# leds.net
KiCad netlist of a schematic drawn in Altium Designer
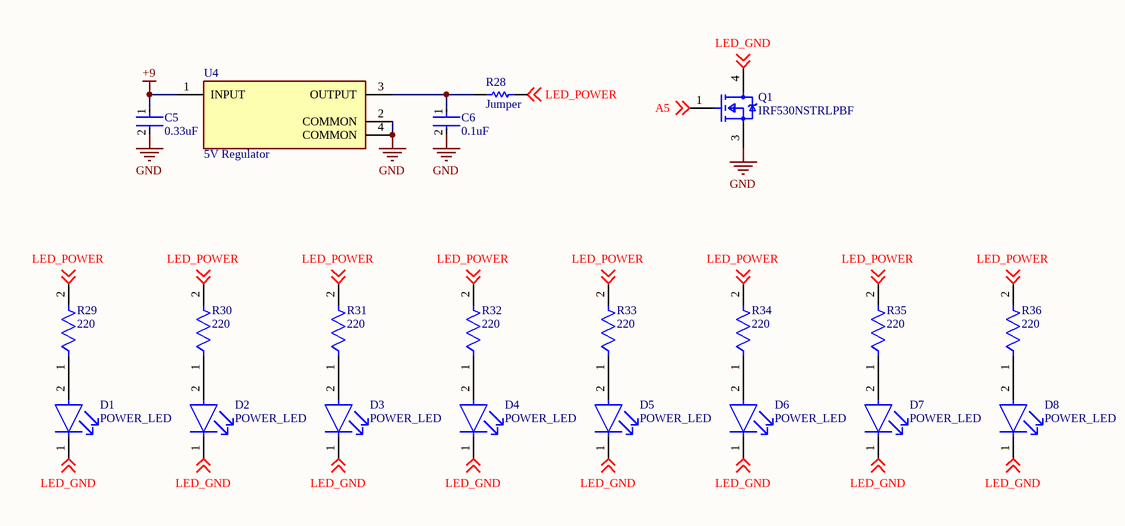
[diagram p0: leds.SchDoc]

(export (version "E")
  (design (tool "Eeschema 10.0.6"))
  (components
    (comp (ref "C5")
      (value "0.33uF")
      (footprint "FP-C0805C-DN-MFG")
      (description "C0805 0.33 μF X7R 30ppm/°C 10.00% 50 V")
      (fields (field (name "MANUFACTURER PART NUMBER") "C0805C334K5RACTU"))
      (libsource (lib "Altium Content Vault") (part "b4654b650e69147ec39a6b967a45e02"))
    )
    (comp (ref "C6")
      (value "0.1uF")
      (footprint "FP-C0805C-DN-MFG")
      (description "CAP CER 0.1UF 50V X7R 0805")
      (fields
        (field (name "MANUFACTURER PART NUMBER") "C0805C104K5RACTU")
        (field (name "MANUFACTURER") "KEMET")
      )
      (libsource (lib "Altium Content Vault") (part "b4654b650e69147ec39a6b967a45e02"))
    )
    (comp (ref "D1")
      (value "POWER_LED")
      (footprint "FP-APTD3216CGCK-MFG")
      (description "LED GREEN CLEAR 2SMD")
      (fields (field (name "MPN") "APTD3216CGCK"))
      (libsource (lib "Altium Content Vault") (part "8706943c75ba83719d021d2fdc84c58"))
    )
    (comp (ref "D2")
      (value "POWER_LED")
      (footprint "FP-APTD3216CGCK-MFG")
      (description "LED GREEN CLEAR 2SMD")
      (fields (field (name "MPN") "APTD3216CGCK"))
      (libsource (lib "Altium Content Vault") (part "8706943c75ba83719d021d2fdc84c58"))
    )
    (comp (ref "D3")
      (value "POWER_LED")
      (footprint "FP-APTD3216CGCK-MFG")
      (description "LED GREEN CLEAR 2SMD")
      (fields (field (name "MPN") "APTD3216CGCK"))
      (libsource (lib "Altium Content Vault") (part "8706943c75ba83719d021d2fdc84c58"))
    )
    (comp (ref "D4")
      (value "POWER_LED")
      (footprint "FP-APTD3216CGCK-MFG")
      (description "LED GREEN CLEAR 2SMD")
      (fields (field (name "MPN") "APTD3216CGCK"))
      (libsource (lib "Altium Content Vault") (part "8706943c75ba83719d021d2fdc84c58"))
    )
    (comp (ref "D5")
      (value "POWER_LED")
      (footprint "FP-APTD3216CGCK-MFG")
      (description "LED GREEN CLEAR 2SMD")
      (fields (field (name "MPN") "APTD3216CGCK"))
      (libsource (lib "Altium Content Vault") (part "8706943c75ba83719d021d2fdc84c58"))
    )
    (comp (ref "D6")
      (value "POWER_LED")
      (footprint "FP-APTD3216CGCK-MFG")
      (description "LED GREEN CLEAR 2SMD")
      (fields (field (name "MPN") "APTD3216CGCK"))
      (libsource (lib "Altium Content Vault") (part "8706943c75ba83719d021d2fdc84c58"))
    )
    (comp (ref "D7")
      (value "POWER_LED")
      (footprint "FP-APTD3216CGCK-MFG")
      (description "LED GREEN CLEAR 2SMD")
      (fields (field (name "MPN") "APTD3216CGCK"))
      (libsource (lib "Altium Content Vault") (part "8706943c75ba83719d021d2fdc84c58"))
    )
    (comp (ref "D8")
      (value "POWER_LED")
      (footprint "FP-APTD3216CGCK-MFG")
      (description "LED GREEN CLEAR 2SMD")
      (fields (field (name "MPN") "APTD3216CGCK"))
      (libsource (lib "Altium Content Vault") (part "8706943c75ba83719d021d2fdc84c58"))
    )
    (comp (ref "Q1")
      (value "IRF530NSTRLPBF")
      (footprint "FP-PG-TO263-3-MFG")
      (description "MOSFET N-CH 100V 17A D2PAK")
      (fields
        (field (name "OCTOPART") "https://octopart.com/irf530nstrlpbf-infineon-65873402")
        (field (name "MANUFACTURER") "Infineon")
      )
      (libsource (lib "Altium Content Vault") (part "cdf1c68f84cb049e5ebc85739c3fcf6"))
    )
    (comp (ref "R28")
      (value "Jumper")
      (footprint "RESC2013X70X40NL20T20")
      (description "Chip Resistor, 0 Ohm, +/- 1%, 0.125 W, -55 to 155 degC, 0805 (2012 Metric), RoHS, Tape and Reel")
      (fields (field (name "PARTNUMBER") "ERJ-6GEY0R00V") (field (name "TOLERANCE") "5%"))
      (libsource (lib "Altium Content Vault") (part "RES-2"))
    )
    (comp (ref "R29")
      (value "220")
      (footprint "FP-CRCW0805-e3-MFG")
      (description "RES Thick Film, 220Ω, 1%, 0.125W, 100ppm/°C, 0805")
      (fields (field (name "TOLERANCE") "1%") (field (name "MPN") "CRCW0805220RFKEA"))
      (libsource (lib "Altium Content Vault") (part "1029c3af85768c4190bb7ad29bc67b5"))
    )
    (comp (ref "R30")
      (value "220")
      (footprint "FP-CRCW0805-e3-MFG")
      (description "RES Thick Film, 220Ω, 1%, 0.125W, 100ppm/°C, 0805")
      (fields (field (name "TOLERANCE") "1%") (field (name "MPN") "CRCW0805220RFKEA"))
      (libsource (lib "Altium Content Vault") (part "1029c3af85768c4190bb7ad29bc67b5"))
    )
    (comp (ref "R31")
      (value "220")
      (footprint "FP-CRCW0805-e3-MFG")
      (description "RES Thick Film, 220Ω, 1%, 0.125W, 100ppm/°C, 0805")
      (fields (field (name "TOLERANCE") "1%") (field (name "MPN") "CRCW0805220RFKEA"))
      (libsource (lib "Altium Content Vault") (part "1029c3af85768c4190bb7ad29bc67b5"))
    )
    (comp (ref "R32")
      (value "220")
      (footprint "FP-CRCW0805-e3-MFG")
      (description "RES Thick Film, 220Ω, 1%, 0.125W, 100ppm/°C, 0805")
      (fields (field (name "TOLERANCE") "1%") (field (name "MPN") "CRCW0805220RFKEA"))
      (libsource (lib "Altium Content Vault") (part "1029c3af85768c4190bb7ad29bc67b5"))
    )
    (comp (ref "R33")
      (value "220")
      (footprint "FP-CRCW0805-e3-MFG")
      (description "RES Thick Film, 220Ω, 1%, 0.125W, 100ppm/°C, 0805")
      (fields (field (name "TOLERANCE") "1%") (field (name "MPN") "CRCW0805220RFKEA"))
      (libsource (lib "Altium Content Vault") (part "1029c3af85768c4190bb7ad29bc67b5"))
    )
    (comp (ref "R34")
      (value "220")
      (footprint "FP-CRCW0805-e3-MFG")
      (description "RES Thick Film, 220Ω, 1%, 0.125W, 100ppm/°C, 0805")
      (fields (field (name "TOLERANCE") "1%") (field (name "MPN") "CRCW0805220RFKEA"))
      (libsource (lib "Altium Content Vault") (part "1029c3af85768c4190bb7ad29bc67b5"))
    )
    (comp (ref "R35")
      (value "220")
      (footprint "FP-CRCW0805-e3-MFG")
      (description "RES Thick Film, 220Ω, 1%, 0.125W, 100ppm/°C, 0805")
      (fields (field (name "TOLERANCE") "1%") (field (name "MPN") "CRCW0805220RFKEA"))
      (libsource (lib "Altium Content Vault") (part "1029c3af85768c4190bb7ad29bc67b5"))
    )
    (comp (ref "R36")
      (value "220")
      (footprint "FP-CRCW0805-e3-MFG")
      (description "RES Thick Film, 220Ω, 1%, 0.125W, 100ppm/°C, 0805")
      (fields (field (name "TOLERANCE") "1%") (field (name "MPN") "CRCW0805220RFKEA"))
      (libsource (lib "Altium Content Vault") (part "1029c3af85768c4190bb7ad29bc67b5"))
    )
    (comp (ref "U4")
      (value "5V Regulator")
      (footprint "FP-KTT0003A-MFG")
      (description "IC REG LIN 5V 1.5A DDPAK/TO263-3")
      (fields (field (name "MPN") "UA7805CKTTR"))
      (libsource (lib "Altium Content Vault") (part "ebcbf24666fa34e59130a841f5280a4"))
    )
  )
  (nets
    (net (code "1") (name "+9") (class "Default")
      (node (ref "C5") (pin "1") (pinfunction "1_1") (pintype "passive"))
      (node (ref "U4") (pin "1") (pinfunction "INPUT_1") (pintype "power_in"))
    )
    (net (code "2") (name "A5") (class "Default")
      (node (ref "Q1") (pin "1") (pinfunction "G_1") (pintype "passive"))
    )
    (net (code "3") (name "GND") (class "Default")
      (node (ref "C5") (pin "2") (pinfunction "2_2") (pintype "passive"))
      (node (ref "C6") (pin "2") (pinfunction "2_2") (pintype "passive"))
      (node (ref "Q1") (pin "3") (pinfunction "S_3") (pintype "passive"))
      (node (ref "U4") (pin "2") (pinfunction "COMMON_2") (pintype "power_in"))
      (node (ref "U4") (pin "4") (pinfunction "COMMON_4") (pintype "power_in"))
    )
    (net (code "4") (name "LED_GND") (class "Default")
      (node (ref "D1") (pin "1") (pinfunction "C_1") (pintype "passive"))
      (node (ref "D2") (pin "1") (pinfunction "C_1") (pintype "passive"))
      (node (ref "D3") (pin "1") (pinfunction "C_1") (pintype "passive"))
      (node (ref "D4") (pin "1") (pinfunction "C_1") (pintype "passive"))
      (node (ref "D5") (pin "1") (pinfunction "C_1") (pintype "passive"))
      (node (ref "D6") (pin "1") (pinfunction "C_1") (pintype "passive"))
      (node (ref "D7") (pin "1") (pinfunction "C_1") (pintype "passive"))
      (node (ref "D8") (pin "1") (pinfunction "C_1") (pintype "passive"))
      (node (ref "Q1") (pin "4") (pinfunction "D_4") (pintype "passive"))
    )
    (net (code "5") (name "LED_POWER") (class "Default")
      (node (ref "R28") (pin "2") (pinfunction "2_2") (pintype "passive"))
      (node (ref "R29") (pin "2") (pinfunction "2_2") (pintype "passive"))
      (node (ref "R30") (pin "2") (pinfunction "2_2") (pintype "passive"))
      (node (ref "R31") (pin "2") (pinfunction "2_2") (pintype "passive"))
      (node (ref "R32") (pin "2") (pinfunction "2_2") (pintype "passive"))
      (node (ref "R33") (pin "2") (pinfunction "2_2") (pintype "passive"))
      (node (ref "R34") (pin "2") (pinfunction "2_2") (pintype "passive"))
      (node (ref "R35") (pin "2") (pinfunction "2_2") (pintype "passive"))
      (node (ref "R36") (pin "2") (pinfunction "2_2") (pintype "passive"))
    )
    (net (code "6") (name "Net-(D1-A)") (class "Default")
      (node (ref "D1") (pin "2") (pinfunction "A_2") (pintype "passive"))
      (node (ref "R29") (pin "1") (pinfunction "1_1") (pintype "passive"))
    )
    (net (code "7") (name "Net-(D2-A)") (class "Default")
      (node (ref "D2") (pin "2") (pinfunction "A_2") (pintype "passive"))
      (node (ref "R30") (pin "1") (pinfunction "1_1") (pintype "passive"))
    )
    (net (code "8") (name "Net-(D3-A)") (class "Default")
      (node (ref "D3") (pin "2") (pinfunction "A_2") (pintype "passive"))
      (node (ref "R31") (pin "1") (pinfunction "1_1") (pintype "passive"))
    )
    (net (code "9") (name "Net-(D4-A)") (class "Default")
      (node (ref "D4") (pin "2") (pinfunction "A_2") (pintype "passive"))
      (node (ref "R32") (pin "1") (pinfunction "1_1") (pintype "passive"))
    )
    (net (code "10") (name "Net-(D5-A)") (class "Default")
      (node (ref "D5") (pin "2") (pinfunction "A_2") (pintype "passive"))
      (node (ref "R33") (pin "1") (pinfunction "1_1") (pintype "passive"))
    )
    (net (code "11") (name "Net-(D6-A)") (class "Default")
      (node (ref "D6") (pin "2") (pinfunction "A_2") (pintype "passive"))
      (node (ref "R34") (pin "1") (pinfunction "1_1") (pintype "passive"))
    )
    (net (code "12") (name "Net-(D7-A)") (class "Default")
      (node (ref "D7") (pin "2") (pinfunction "A_2") (pintype "passive"))
      (node (ref "R35") (pin "1") (pinfunction "1_1") (pintype "passive"))
    )
    (net (code "13") (name "Net-(D8-A)") (class "Default")
      (node (ref "D8") (pin "2") (pinfunction "A_2") (pintype "passive"))
      (node (ref "R36") (pin "1") (pinfunction "1_1") (pintype "passive"))
    )
    (net (code "14") (name "Net-(U4-OUTPUT)") (class "Default")
      (node (ref "C6") (pin "1") (pinfunction "1_1") (pintype "passive"))
      (node (ref "R28") (pin "1") (pinfunction "1_1") (pintype "passive"))
      (node (ref "U4") (pin "3") (pinfunction "OUTPUT_3") (pintype "power_in"))
    )
  )
)
